# Logic_Voltage_Source.net
KiCad netlist of a schematic drawn in Altium Designer
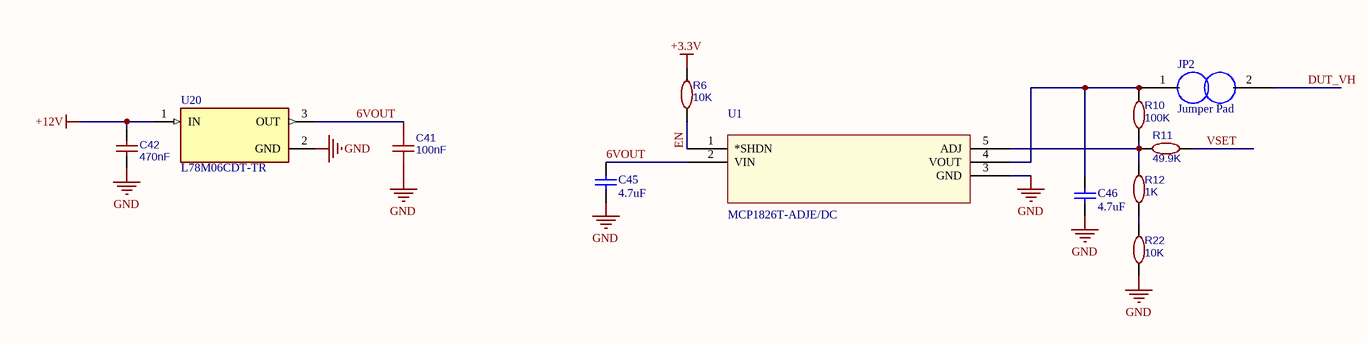
[diagram p0: Logic Voltage Source.SchDoc]

(export (version "E")
  (design (tool "Eeschema 10.0.6"))
  (components
    (comp (ref "C41")
      (value "100nF")
      (footprint "C0603")
      (fields
        (field (name "MANUFACTURER") "YAGEO")
        (field (name "MANUFACTURE PART NUMBER") "CC0603KRX7R9BB104")
      )
      (libsource (lib "Main_MCU") (part "100nF"))
    )
    (comp (ref "C42")
      (value "470nF")
      (footprint "C0603")
      (fields
        (field (name "MANUFACTURER") "WTC")
        (field (name "MANUFACTURE PART NUMBER") "0603B474K100")
        (field (name "CONTRIBUTOR") "LCSC")
      )
      (libsource (lib "Main_MCU") (part "470nF"))
    )
    (comp (ref "C45")
      (value "4.7uF")
      (footprint "CAPC1608X09N")
      (description "0603 10 nF 50 V ± 10% Tolerance X7R Surface Mount Multilayer Ceramic Capacitor")
      (fields
        (field (name "MANUFACTURE PART NUMBER") "CL10A475KP8NNNC")
        (field (name "MANUFACTURER") "Samsung Electro-Mechanics")
      )
      (libsource (lib "Resistor Capacitor") (part "CMP-2f55e5122ad9f092-5_3"))
    )
    (comp (ref "C46")
      (value "4.7uF")
      (footprint "CAPC1608X09N")
      (description "0603 10 nF 50 V ± 10% Tolerance X7R Surface Mount Multilayer Ceramic Capacitor")
      (fields
        (field (name "MANUFACTURE PART NUMBER") "CL10A475KP8NNNC")
        (field (name "MANUFACTURER") "Samsung Electro-Mechanics")
      )
      (libsource (lib "Resistor Capacitor") (part "CMP-2f55e5122ad9f092-5_3"))
    )
    (comp (ref "JP2")
      (value "Jumper Pad")
      (footprint "PCB-sjva3kmaxrqfkswkvsp7-1")
      (description "JP")
      (libsource (lib "POWER CARD") (part "CMP-75tq5o8j4p0avfd6ylbk-1"))
    )
    (comp (ref "R6")
      (value "10K")
      (footprint "R0603")
      (fields
        (field (name "MANUFACTURER") "YAGEO")
        (field (name "MANUFACTURE PART NUMBER") "RC0603FR-0710KL")
      )
      (libsource (lib "Main_MCU") (part "10K"))
    )
    (comp (ref "R10")
      (value "100K")
      (footprint "R0603")
      (fields
        (field (name "MANUFACTURER") "UniOhm")
        (field (name "MANUFACTURE PART NUMBER") "0603WAF1003T5E")
      )
      (libsource (lib "FPGA Interface Board") (part "100K"))
    )
    (comp (ref "R11")
      (value "49.9K")
      (footprint "R0603")
      (fields
        (field (name "MANUFACTURER") "UniOhm")
        (field (name "MANUFACTURE PART NUMBER") "0603WAF4992T5E")
      )
      (libsource (lib "FPGA Interface Board") (part "49.9K"))
    )
    (comp (ref "R12")
      (value "1K")
      (footprint "R0603")
      (fields (field (name "MANUFACTURE PART NUMBER") "RC0603FR-071KL") (field (name "MANUFACTURER") "YAGEO"))
      (libsource (lib "Main_MCU") (part "1K"))
    )
    (comp (ref "R22")
      (value "10K")
      (footprint "R0603")
      (fields
        (field (name "MANUFACTURER") "YAGEO")
        (field (name "MANUFACTURE PART NUMBER") "RC0603FR-0710KL")
      )
      (libsource (lib "Main_MCU") (part "10K"))
    )
    (comp (ref "U1")
      (value "MCP1826T-ADJE/DC")
      (footprint "MCP1826T-ADJE/DC")
      (description "Adjustable 6V 0.8V ~ 5V 400mV @ 1A SOT-223-6 Dropout Regulators(LDO) RoHS")
      (fields (field (name "MANUFACTURER") "Microchip Tech"))
      (libsource (lib "FPGA Interface Board") (part "MCP1826T-ADJE/DC"))
    )
    (comp (ref "U20")
      (value "L78M06CDT-TR")
      (footprint "VREG_L78M06CDT-TR")
      (description "Linear Voltage Regulator IC 1 Output 500mA DPAK")
      (fields (field (name "MANUFACTURER") "STMicroelectronics"))
      (libsource (lib "FPGA Interface Board") (part "L78M06CDT-TR"))
    )
  )
  (nets
    (net (code "1") (name "+3.3V") (class "Default")
      (node (ref "R6") (pin "2") (pinfunction "2_2") (pintype "passive"))
    )
    (net (code "2") (name "+12V") (class "Default")
      (node (ref "C42") (pin "2") (pinfunction "2_2") (pintype "passive"))
      (node (ref "U20") (pin "1") (pinfunction "IN_1") (pintype "input"))
    )
    (net (code "3") (name "/6VOUT") (class "Default")
      (node (ref "C41") (pin "2") (pinfunction "2_2") (pintype "passive"))
      (node (ref "C45") (pin "2") (pinfunction "2_2") (pintype "passive"))
      (node (ref "U1") (pin "2") (pinfunction "VIN_2") (pintype "passive"))
      (node (ref "U20") (pin "3") (pinfunction "OUT_3") (pintype "output"))
    )
    (net (code "4") (name "/DUT_VH") (class "Default") (node (ref "JP2") (pin "2") (pintype "passive")))
    (net (code "5") (name "/EN") (class "Default")
      (node (ref "R6") (pin "1") (pinfunction "1_1") (pintype "passive"))
      (node (ref "U1") (pin "1") (pinfunction "*SHDN_1") (pintype "passive"))
    )
    (net (code "6") (name "/VSET") (class "Default")
      (node (ref "R11") (pin "2") (pinfunction "2_2") (pintype "passive"))
    )
    (net (code "7") (name "GND") (class "Default")
      (node (ref "C41") (pin "1") (pinfunction "1_1") (pintype "passive"))
      (node (ref "C42") (pin "1") (pinfunction "1_1") (pintype "passive"))
      (node (ref "C45") (pin "1") (pinfunction "1_1") (pintype "passive"))
      (node (ref "C46") (pin "1") (pinfunction "1_1") (pintype "passive"))
      (node (ref "R22") (pin "1") (pinfunction "1_1") (pintype "passive"))
      (node (ref "U1") (pin "3") (pinfunction "GND_3") (pintype "passive"))
      (node (ref "U20") (pin "2") (pinfunction "GND_2") (pintype "power_in"))
    )
    (net (code "8") (name "Net-(R12-Pad1)") (class "Default")
      (node (ref "R12") (pin "1") (pinfunction "1_1") (pintype "passive"))
      (node (ref "R22") (pin "2") (pinfunction "2_2") (pintype "passive"))
    )
    (net (code "9") (name "Net-(U1-ADJ)") (class "Default")
      (node (ref "R10") (pin "1") (pinfunction "1_1") (pintype "passive"))
      (node (ref "R11") (pin "1") (pinfunction "1_1") (pintype "passive"))
      (node (ref "R12") (pin "2") (pinfunction "2_2") (pintype "passive"))
      (node (ref "U1") (pin "5") (pinfunction "ADJ_5") (pintype "passive"))
    )
    (net (code "10") (name "Net-(U1-VOUT)") (class "Default")
      (node (ref "C46") (pin "2") (pinfunction "2_2") (pintype "passive"))
      (node (ref "JP2") (pin "1") (pintype "passive"))
      (node (ref "R10") (pin "2") (pinfunction "2_2") (pintype "passive"))
      (node (ref "U1") (pin "4") (pinfunction "VOUT_4") (pintype "passive"))
    )
  )
)
